# atmega16_laptop_keyboard.net
KiCad netlist of a schematic drawn in EAGLE
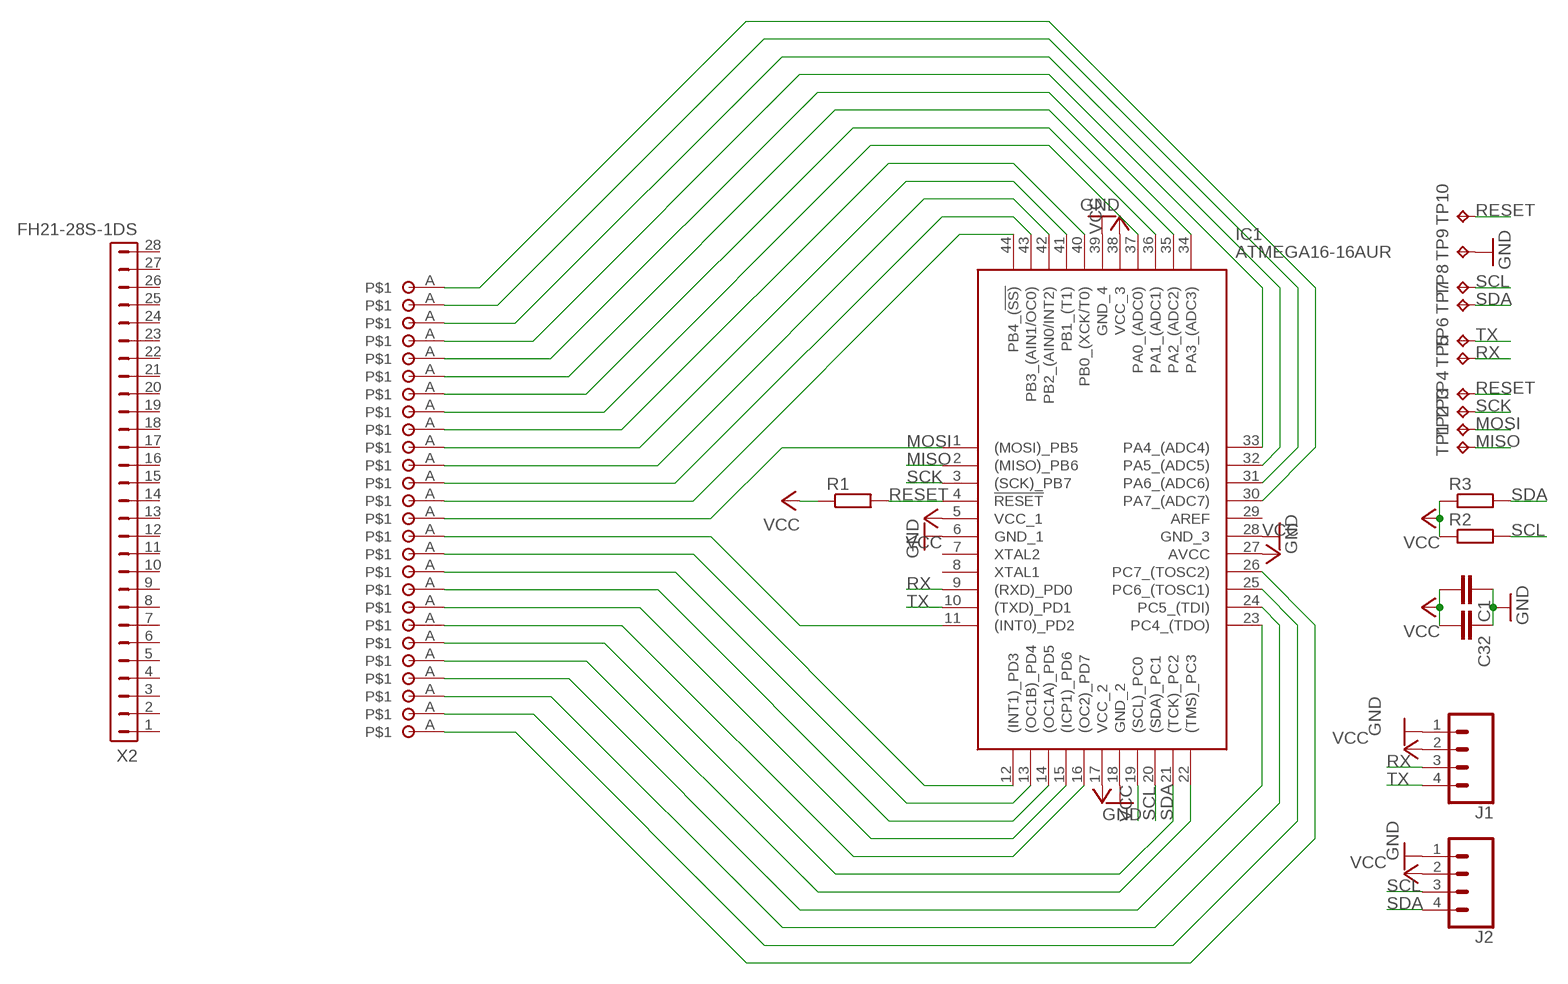
[diagram p0: schematic, sheet 1]

(export (version "E")
  (design (tool "Eeschema 10.0.6"))
  (components
    (comp (ref "C1")
      (value "C-EUC0805")
      (footprint "eagle-import:C0805")
      (libsource (lib "eagle-import") (part "C-EUC0805"))
    )
    (comp (ref "C32")
      (value "C-EUC0805")
      (footprint "eagle-import:C0805")
      (libsource (lib "eagle-import") (part "C-EUC0805"))
    )
    (comp (ref "IC1")
      (value "ATMEGA16-16AUR")
      (footprint "eagle-import:QFP80P1200X1200X120-44N")
      (fields (field (name "MOUSER_PART_NUMBER") "556-ATMEGA16-16AUR"))
      (libsource (lib "eagle-import") (part "ATMEGA16-16AUR"))
    )
    (comp (ref "J1")
      (value "CONN_04LONGPADS")
      (footprint "eagle-import:1X04_LONGPADS")
      (libsource (lib "eagle-import") (part "CONN_04LONGPADS"))
    )
    (comp (ref "J2")
      (value "CONN_04LONGPADS")
      (footprint "eagle-import:1X04_LONGPADS")
      (libsource (lib "eagle-import") (part "CONN_04LONGPADS"))
    )
    (comp (ref "R1")
      (value "R-EU_M0805")
      (footprint "eagle-import:M0805")
      (libsource (lib "eagle-import") (part "R-EU_M0805"))
    )
    (comp (ref "R2")
      (value "R-EU_M0805")
      (footprint "eagle-import:M0805")
      (libsource (lib "eagle-import") (part "R-EU_M0805"))
    )
    (comp (ref "R3")
      (value "R-EU_M0805")
      (footprint "eagle-import:M0805")
      (libsource (lib "eagle-import") (part "R-EU_M0805"))
    )
    (comp (ref "TP1")
      (value "TPTP15R")
      (footprint "eagle-import:TP15R")
      (libsource (lib "eagle-import") (part "TPTP15R"))
    )
    (comp (ref "TP2")
      (value "TPTP15R")
      (footprint "eagle-import:TP15R")
      (libsource (lib "eagle-import") (part "TPTP15R"))
    )
    (comp (ref "TP3")
      (value "TPTP15R")
      (footprint "eagle-import:TP15R")
      (libsource (lib "eagle-import") (part "TPTP15R"))
    )
    (comp (ref "TP4")
      (value "TPTP15R")
      (footprint "eagle-import:TP15R")
      (libsource (lib "eagle-import") (part "TPTP15R"))
    )
    (comp (ref "TP5")
      (value "TPTP15R")
      (footprint "eagle-import:TP15R")
      (libsource (lib "eagle-import") (part "TPTP15R"))
    )
    (comp (ref "TP6")
      (value "TPTP15R")
      (footprint "eagle-import:TP15R")
      (libsource (lib "eagle-import") (part "TPTP15R"))
    )
    (comp (ref "TP7")
      (value "TPTP15R")
      (footprint "eagle-import:TP15R")
      (libsource (lib "eagle-import") (part "TPTP15R"))
    )
    (comp (ref "TP8")
      (value "TPTP15R")
      (footprint "eagle-import:TP15R")
      (libsource (lib "eagle-import") (part "TPTP15R"))
    )
    (comp (ref "TP9")
      (value "TPTP15R")
      (footprint "eagle-import:TP15R")
      (libsource (lib "eagle-import") (part "TPTP15R"))
    )
    (comp (ref "TP10")
      (value "TPTP15R")
      (footprint "eagle-import:TP15R")
      (libsource (lib "eagle-import") (part "TPTP15R"))
    )
    (comp (ref "U$1")
      (value "PAD1")
      (footprint "eagle-import:PAD1")
      (libsource (lib "eagle-import") (part "PAD1"))
    )
    (comp (ref "U$2")
      (value "PAD1")
      (footprint "eagle-import:PAD1")
      (libsource (lib "eagle-import") (part "PAD1"))
    )
    (comp (ref "U$3")
      (value "PAD1")
      (footprint "eagle-import:PAD1")
      (libsource (lib "eagle-import") (part "PAD1"))
    )
    (comp (ref "U$4")
      (value "PAD1")
      (footprint "eagle-import:PAD1")
      (libsource (lib "eagle-import") (part "PAD1"))
    )
    (comp (ref "U$5")
      (value "PAD1")
      (footprint "eagle-import:PAD1")
      (libsource (lib "eagle-import") (part "PAD1"))
    )
    (comp (ref "U$6")
      (value "PAD1")
      (footprint "eagle-import:PAD1")
      (libsource (lib "eagle-import") (part "PAD1"))
    )
    (comp (ref "U$7")
      (value "PAD1")
      (footprint "eagle-import:PAD1")
      (libsource (lib "eagle-import") (part "PAD1"))
    )
    (comp (ref "U$8")
      (value "PAD1")
      (footprint "eagle-import:PAD1")
      (libsource (lib "eagle-import") (part "PAD1"))
    )
    (comp (ref "U$9")
      (value "PAD1")
      (footprint "eagle-import:PAD1")
      (libsource (lib "eagle-import") (part "PAD1"))
    )
    (comp (ref "U$10")
      (value "PAD1")
      (footprint "eagle-import:PAD1")
      (libsource (lib "eagle-import") (part "PAD1"))
    )
    (comp (ref "U$11")
      (value "PAD1")
      (footprint "eagle-import:PAD1")
      (libsource (lib "eagle-import") (part "PAD1"))
    )
    (comp (ref "U$12")
      (value "PAD1")
      (footprint "eagle-import:PAD1")
      (libsource (lib "eagle-import") (part "PAD1"))
    )
    (comp (ref "U$13")
      (value "PAD1")
      (footprint "eagle-import:PAD1")
      (libsource (lib "eagle-import") (part "PAD1"))
    )
    (comp (ref "U$14")
      (value "PAD1")
      (footprint "eagle-import:PAD1")
      (libsource (lib "eagle-import") (part "PAD1"))
    )
    (comp (ref "U$15")
      (value "PAD1")
      (footprint "eagle-import:PAD1")
      (libsource (lib "eagle-import") (part "PAD1"))
    )
    (comp (ref "U$16")
      (value "PAD1")
      (footprint "eagle-import:PAD1")
      (libsource (lib "eagle-import") (part "PAD1"))
    )
    (comp (ref "U$17")
      (value "PAD1")
      (footprint "eagle-import:PAD1")
      (libsource (lib "eagle-import") (part "PAD1"))
    )
    (comp (ref "U$18")
      (value "PAD1")
      (footprint "eagle-import:PAD1")
      (libsource (lib "eagle-import") (part "PAD1"))
    )
    (comp (ref "U$19")
      (value "PAD1")
      (footprint "eagle-import:PAD1")
      (libsource (lib "eagle-import") (part "PAD1"))
    )
    (comp (ref "U$20")
      (value "PAD1")
      (footprint "eagle-import:PAD1")
      (libsource (lib "eagle-import") (part "PAD1"))
    )
    (comp (ref "U$21")
      (value "PAD1")
      (footprint "eagle-import:PAD1")
      (libsource (lib "eagle-import") (part "PAD1"))
    )
    (comp (ref "U$22")
      (value "PAD1")
      (footprint "eagle-import:PAD1")
      (libsource (lib "eagle-import") (part "PAD1"))
    )
    (comp (ref "U$23")
      (value "PAD1")
      (footprint "eagle-import:PAD1")
      (libsource (lib "eagle-import") (part "PAD1"))
    )
    (comp (ref "U$24")
      (value "PAD1")
      (footprint "eagle-import:PAD1")
      (libsource (lib "eagle-import") (part "PAD1"))
    )
    (comp (ref "U$25")
      (value "PAD1")
      (footprint "eagle-import:PAD1")
      (libsource (lib "eagle-import") (part "PAD1"))
    )
    (comp (ref "U$26")
      (value "PAD1")
      (footprint "eagle-import:PAD1")
      (libsource (lib "eagle-import") (part "PAD1"))
    )
    (comp (ref "X2")
      (value "FH21-28S-1DS")
      (footprint "eagle-import:FH21-28S-1DS")
      (libsource (lib "eagle-import") (part "FH21-28S-1DS"))
    )
  )
  (nets
    (net (code "1") (name "/MISO") (class "Default")
      (node (ref "IC1") (pin "2") (pinfunction "(MISO)_PB6_2") (pintype "bidirectional"))
      (node (ref "TP1") (pin "TP") (pinfunction "TP_TP") (pintype "input"))
    )
    (net (code "2") (name "/MOSI") (class "Default")
      (node (ref "IC1") (pin "1") (pinfunction "(MOSI)_PB5_1") (pintype "bidirectional"))
      (node (ref "TP2") (pin "TP") (pinfunction "TP_TP") (pintype "input"))
      (node (ref "U$14") (pin "A") (pinfunction "P$1_A") (pintype "bidirectional"))
    )
    (net (code "3") (name "/RESET") (class "Default")
      (node (ref "IC1") (pin "4") (pinfunction "~{RESET}_4") (pintype "bidirectional"))
      (node (ref "R1") (pin "2") (pinfunction "2_2") (pintype "passive"))
      (node (ref "TP10") (pin "TP") (pinfunction "TP_TP") (pintype "input"))
      (node (ref "TP4") (pin "TP") (pinfunction "TP_TP") (pintype "input"))
    )
    (net (code "4") (name "/RX") (class "Default")
      (node (ref "IC1") (pin "9") (pinfunction "(RXD)_PD0_9") (pintype "bidirectional"))
      (node (ref "J1") (pin "3") (pinfunction "3_3") (pintype "passive"))
      (node (ref "TP5") (pin "TP") (pinfunction "TP_TP") (pintype "input"))
    )
    (net (code "5") (name "/SCK") (class "Default")
      (node (ref "IC1") (pin "3") (pinfunction "(SCK)_PB7_3") (pintype "bidirectional"))
      (node (ref "TP3") (pin "TP") (pinfunction "TP_TP") (pintype "input"))
    )
    (net (code "6") (name "/SCL") (class "Default")
      (node (ref "IC1") (pin "19") (pinfunction "(SCL)_PC0_19") (pintype "bidirectional"))
      (node (ref "J2") (pin "3") (pinfunction "3_3") (pintype "passive"))
      (node (ref "R2") (pin "2") (pinfunction "2_2") (pintype "passive"))
      (node (ref "TP8") (pin "TP") (pinfunction "TP_TP") (pintype "input"))
    )
    (net (code "7") (name "/SDA") (class "Default")
      (node (ref "IC1") (pin "20") (pinfunction "(SDA)_PC1_20") (pintype "bidirectional"))
      (node (ref "J2") (pin "4") (pinfunction "4_4") (pintype "passive"))
      (node (ref "R3") (pin "2") (pinfunction "2_2") (pintype "passive"))
      (node (ref "TP7") (pin "TP") (pinfunction "TP_TP") (pintype "input"))
    )
    (net (code "8") (name "/TX") (class "Default")
      (node (ref "IC1") (pin "10") (pinfunction "(TXD)_PD1_10") (pintype "bidirectional"))
      (node (ref "J1") (pin "4") (pinfunction "4_4") (pintype "passive"))
      (node (ref "TP6") (pin "TP") (pinfunction "TP_TP") (pintype "input"))
    )
    (net (code "9") (name "GND") (class "Default")
      (node (ref "C1") (pin "1") (pinfunction "1_1") (pintype "passive"))
      (node (ref "C32") (pin "1") (pinfunction "1_1") (pintype "passive"))
      (node (ref "IC1") (pin "18") (pinfunction "GND_2_18") (pintype "bidirectional"))
      (node (ref "IC1") (pin "28") (pinfunction "GND_3_28") (pintype "bidirectional"))
      (node (ref "IC1") (pin "39") (pinfunction "GND_4_39") (pintype "bidirectional"))
      (node (ref "IC1") (pin "6") (pinfunction "GND_1_6") (pintype "bidirectional"))
      (node (ref "J1") (pin "1") (pinfunction "1_1") (pintype "passive"))
      (node (ref "J2") (pin "1") (pinfunction "1_1") (pintype "passive"))
      (node (ref "TP9") (pin "TP") (pinfunction "TP_TP") (pintype "input"))
    )
    (net (code "10") (name "Net-(IC1-(ICP1)_PD6)") (class "Default")
      (node (ref "IC1") (pin "15") (pinfunction "(ICP1)_PD6_15") (pintype "bidirectional"))
      (node (ref "U$19") (pin "A") (pinfunction "P$1_A") (pintype "bidirectional"))
    )
    (net (code "11") (name "Net-(IC1-(INT0)_PD2)") (class "Default")
      (node (ref "IC1") (pin "11") (pinfunction "(INT0)_PD2_11") (pintype "bidirectional"))
      (node (ref "U$15") (pin "A") (pinfunction "P$1_A") (pintype "bidirectional"))
    )
    (net (code "12") (name "Net-(IC1-(INT1)_PD3)") (class "Default")
      (node (ref "IC1") (pin "12") (pinfunction "(INT1)_PD3_12") (pintype "bidirectional"))
      (node (ref "U$16") (pin "A") (pinfunction "P$1_A") (pintype "bidirectional"))
    )
    (net (code "13") (name "Net-(IC1-(OC1A)_PD5)") (class "Default")
      (node (ref "IC1") (pin "14") (pinfunction "(OC1A)_PD5_14") (pintype "bidirectional"))
      (node (ref "U$18") (pin "A") (pinfunction "P$1_A") (pintype "bidirectional"))
    )
    (net (code "14") (name "Net-(IC1-(OC1B)_PD4)") (class "Default")
      (node (ref "IC1") (pin "13") (pinfunction "(OC1B)_PD4_13") (pintype "bidirectional"))
      (node (ref "U$17") (pin "A") (pinfunction "P$1_A") (pintype "bidirectional"))
    )
    (net (code "15") (name "Net-(IC1-(OC2)_PD7)") (class "Default")
      (node (ref "IC1") (pin "16") (pinfunction "(OC2)_PD7_16") (pintype "bidirectional"))
      (node (ref "U$20") (pin "A") (pinfunction "P$1_A") (pintype "bidirectional"))
    )
    (net (code "16") (name "Net-(IC1-(TCK)_PC2)") (class "Default")
      (node (ref "IC1") (pin "21") (pinfunction "(TCK)_PC2_21") (pintype "bidirectional"))
      (node (ref "U$21") (pin "A") (pinfunction "P$1_A") (pintype "bidirectional"))
    )
    (net (code "17") (name "Net-(IC1-(TMS)_PC3)") (class "Default")
      (node (ref "IC1") (pin "22") (pinfunction "(TMS)_PC3_22") (pintype "bidirectional"))
      (node (ref "U$22") (pin "A") (pinfunction "P$1_A") (pintype "bidirectional"))
    )
    (net (code "18") (name "Net-(IC1-PA0_(ADC0))") (class "Default")
      (node (ref "IC1") (pin "37") (pinfunction "PA0_(ADC0)_37") (pintype "bidirectional"))
      (node (ref "U$8") (pin "A") (pinfunction "P$1_A") (pintype "bidirectional"))
    )
    (net (code "19") (name "Net-(IC1-PA1_(ADC1))") (class "Default")
      (node (ref "IC1") (pin "36") (pinfunction "PA1_(ADC1)_36") (pintype "bidirectional"))
      (node (ref "U$7") (pin "A") (pinfunction "P$1_A") (pintype "bidirectional"))
    )
    (net (code "20") (name "Net-(IC1-PA2_(ADC2))") (class "Default")
      (node (ref "IC1") (pin "35") (pinfunction "PA2_(ADC2)_35") (pintype "bidirectional"))
      (node (ref "U$6") (pin "A") (pinfunction "P$1_A") (pintype "bidirectional"))
    )
    (net (code "21") (name "Net-(IC1-PA3_(ADC3))") (class "Default")
      (node (ref "IC1") (pin "34") (pinfunction "PA3_(ADC3)_34") (pintype "bidirectional"))
      (node (ref "U$5") (pin "A") (pinfunction "P$1_A") (pintype "bidirectional"))
    )
    (net (code "22") (name "Net-(IC1-PA4_(ADC4))") (class "Default")
      (node (ref "IC1") (pin "33") (pinfunction "PA4_(ADC4)_33") (pintype "bidirectional"))
      (node (ref "U$4") (pin "A") (pinfunction "P$1_A") (pintype "bidirectional"))
    )
    (net (code "23") (name "Net-(IC1-PA5_(ADC5))") (class "Default")
      (node (ref "IC1") (pin "32") (pinfunction "PA5_(ADC5)_32") (pintype "bidirectional"))
      (node (ref "U$3") (pin "A") (pinfunction "P$1_A") (pintype "bidirectional"))
    )
    (net (code "24") (name "Net-(IC1-PA6_(ADC6))") (class "Default")
      (node (ref "IC1") (pin "31") (pinfunction "PA6_(ADC6)_31") (pintype "bidirectional"))
      (node (ref "U$2") (pin "A") (pinfunction "P$1_A") (pintype "bidirectional"))
    )
    (net (code "25") (name "Net-(IC1-PA7_(ADC7))") (class "Default")
      (node (ref "IC1") (pin "30") (pinfunction "PA7_(ADC7)_30") (pintype "bidirectional"))
      (node (ref "U$1") (pin "A") (pinfunction "P$1_A") (pintype "bidirectional"))
    )
    (net (code "26") (name "Net-(IC1-PB0_(XCK{slash}T0))") (class "Default")
      (node (ref "IC1") (pin "40") (pinfunction "PB0_(XCK/T0)_40") (pintype "bidirectional"))
      (node (ref "U$9") (pin "A") (pinfunction "P$1_A") (pintype "bidirectional"))
    )
    (net (code "27") (name "Net-(IC1-PB1_(T1))") (class "Default")
      (node (ref "IC1") (pin "41") (pinfunction "PB1_(T1)_41") (pintype "bidirectional"))
      (node (ref "U$10") (pin "A") (pinfunction "P$1_A") (pintype "bidirectional"))
    )
    (net (code "28") (name "Net-(IC1-PB2_(AIN0{slash}INT2))") (class "Default")
      (node (ref "IC1") (pin "42") (pinfunction "PB2_(AIN0/INT2)_42") (pintype "bidirectional"))
      (node (ref "U$11") (pin "A") (pinfunction "P$1_A") (pintype "bidirectional"))
    )
    (net (code "29") (name "Net-(IC1-PB3_(AIN1{slash}OC0))") (class "Default")
      (node (ref "IC1") (pin "43") (pinfunction "PB3_(AIN1/OC0)_43") (pintype "bidirectional"))
      (node (ref "U$12") (pin "A") (pinfunction "P$1_A") (pintype "bidirectional"))
    )
    (net (code "30") (name "Net-(IC1-PB4_(~{SS}))") (class "Default")
      (node (ref "IC1") (pin "44") (pinfunction "PB4_(~{SS})_44") (pintype "bidirectional"))
      (node (ref "U$13") (pin "A") (pinfunction "P$1_A") (pintype "bidirectional"))
    )
    (net (code "31") (name "Net-(IC1-PC4_(TDO))") (class "Default")
      (node (ref "IC1") (pin "23") (pinfunction "PC4_(TDO)_23") (pintype "bidirectional"))
      (node (ref "U$23") (pin "A") (pinfunction "P$1_A") (pintype "bidirectional"))
    )
    (net (code "32") (name "Net-(IC1-PC5_(TDI))") (class "Default")
      (node (ref "IC1") (pin "24") (pinfunction "PC5_(TDI)_24") (pintype "bidirectional"))
      (node (ref "U$24") (pin "A") (pinfunction "P$1_A") (pintype "bidirectional"))
    )
    (net (code "33") (name "Net-(IC1-PC6_(TOSC1))") (class "Default")
      (node (ref "IC1") (pin "25") (pinfunction "PC6_(TOSC1)_25") (pintype "bidirectional"))
      (node (ref "U$25") (pin "A") (pinfunction "P$1_A") (pintype "bidirectional"))
    )
    (net (code "34") (name "Net-(IC1-PC7_(TOSC2))") (class "Default")
      (node (ref "IC1") (pin "26") (pinfunction "PC7_(TOSC2)_26") (pintype "bidirectional"))
      (node (ref "U$26") (pin "A") (pinfunction "P$1_A") (pintype "bidirectional"))
    )
    (net (code "35") (name "VCC") (class "Default")
      (node (ref "C1") (pin "2") (pinfunction "2_2") (pintype "passive"))
      (node (ref "C32") (pin "2") (pinfunction "2_2") (pintype "passive"))
      (node (ref "IC1") (pin "17") (pinfunction "VCC_2_17") (pintype "bidirectional"))
      (node (ref "IC1") (pin "27") (pinfunction "AVCC_27") (pintype "bidirectional"))
      (node (ref "IC1") (pin "38") (pinfunction "VCC_3_38") (pintype "bidirectional"))
      (node (ref "IC1") (pin "5") (pinfunction "VCC_1_5") (pintype "bidirectional"))
      (node (ref "J1") (pin "2") (pinfunction "2_2") (pintype "passive"))
      (node (ref "J2") (pin "2") (pinfunction "2_2") (pintype "passive"))
      (node (ref "R1") (pin "1") (pinfunction "1_1") (pintype "passive"))
      (node (ref "R2") (pin "1") (pinfunction "1_1") (pintype "passive"))
      (node (ref "R3") (pin "1") (pinfunction "1_1") (pintype "passive"))
    )
    (net (code "36") (name "unconnected-(IC1-AREF-Pad29)") (class "Default")
      (node (ref "IC1") (pin "29") (pinfunction "AREF_29") (pintype "bidirectional"))
    )
    (net (code "37") (name "unconnected-(IC1-XTAL1-Pad8)") (class "Default")
      (node (ref "IC1") (pin "8") (pinfunction "XTAL1_8") (pintype "bidirectional"))
    )
    (net (code "38") (name "unconnected-(IC1-XTAL2-Pad7)") (class "Default")
      (node (ref "IC1") (pin "7") (pinfunction "XTAL2_7") (pintype "bidirectional"))
    )
    (net (code "39") (name "unconnected-(X2-Pad1)") (class "Default")
      (node (ref "X2") (pin "1") (pinfunction "1_1") (pintype "passive"))
    )
    (net (code "40") (name "unconnected-(X2-Pad2)") (class "Default")
      (node (ref "X2") (pin "2") (pinfunction "2_2") (pintype "passive"))
    )
    (net (code "41") (name "unconnected-(X2-Pad3)") (class "Default")
      (node (ref "X2") (pin "3") (pinfunction "3_3") (pintype "passive"))
    )
    (net (code "42") (name "unconnected-(X2-Pad4)") (class "Default")
      (node (ref "X2") (pin "4") (pinfunction "4_4") (pintype "passive"))
    )
    (net (code "43") (name "unconnected-(X2-Pad5)") (class "Default")
      (node (ref "X2") (pin "5") (pinfunction "5_5") (pintype "passive"))
    )
    (net (code "44") (name "unconnected-(X2-Pad6)") (class "Default")
      (node (ref "X2") (pin "6") (pinfunction "6_6") (pintype "passive"))
    )
    (net (code "45") (name "unconnected-(X2-Pad7)") (class "Default")
      (node (ref "X2") (pin "7") (pinfunction "7_7") (pintype "passive"))
    )
    (net (code "46") (name "unconnected-(X2-Pad8)") (class "Default")
      (node (ref "X2") (pin "8") (pinfunction "8_8") (pintype "passive"))
    )
    (net (code "47") (name "unconnected-(X2-Pad9)") (class "Default")
      (node (ref "X2") (pin "9") (pinfunction "9_9") (pintype "passive"))
    )
    (net (code "48") (name "unconnected-(X2-Pad10)") (class "Default")
      (node (ref "X2") (pin "10") (pinfunction "10_10") (pintype "passive"))
    )
    (net (code "49") (name "unconnected-(X2-Pad11)") (class "Default")
      (node (ref "X2") (pin "11") (pinfunction "11_11") (pintype "passive"))
    )
    (net (code "50") (name "unconnected-(X2-Pad12)") (class "Default")
      (node (ref "X2") (pin "12") (pinfunction "12_12") (pintype "passive"))
    )
    (net (code "51") (name "unconnected-(X2-Pad13)") (class "Default")
      (node (ref "X2") (pin "13") (pinfunction "13_13") (pintype "passive"))
    )
    (net (code "52") (name "unconnected-(X2-Pad14)") (class "Default")
      (node (ref "X2") (pin "14") (pinfunction "14_14") (pintype "passive"))
    )
    (net (code "53") (name "unconnected-(X2-Pad15)") (class "Default")
      (node (ref "X2") (pin "15") (pinfunction "15_15") (pintype "passive"))
    )
    (net (code "54") (name "unconnected-(X2-Pad16)") (class "Default")
      (node (ref "X2") (pin "16") (pinfunction "16_16") (pintype "passive"))
    )
    (net (code "55") (name "unconnected-(X2-Pad17)") (class "Default")
      (node (ref "X2") (pin "17") (pinfunction "17_17") (pintype "passive"))
    )
    (net (code "56") (name "unconnected-(X2-Pad18)") (class "Default")
      (node (ref "X2") (pin "18") (pinfunction "18_18") (pintype "passive"))
    )
    (net (code "57") (name "unconnected-(X2-Pad19)") (class "Default")
      (node (ref "X2") (pin "19") (pinfunction "19_19") (pintype "passive"))
    )
    (net (code "58") (name "unconnected-(X2-Pad20)") (class "Default")
      (node (ref "X2") (pin "20") (pinfunction "20_20") (pintype "passive"))
    )
    (net (code "59") (name "unconnected-(X2-Pad21)") (class "Default")
      (node (ref "X2") (pin "21") (pinfunction "21_21") (pintype "passive"))
    )
    (net (code "60") (name "unconnected-(X2-Pad22)") (class "Default")
      (node (ref "X2") (pin "22") (pinfunction "22_22") (pintype "passive"))
    )
    (net (code "61") (name "unconnected-(X2-Pad23)") (class "Default")
      (node (ref "X2") (pin "23") (pinfunction "23_23") (pintype "passive"))
    )
    (net (code "62") (name "unconnected-(X2-Pad24)") (class "Default")
      (node (ref "X2") (pin "24") (pinfunction "24_24") (pintype "passive"))
    )
    (net (code "63") (name "unconnected-(X2-Pad25)") (class "Default")
      (node (ref "X2") (pin "25") (pinfunction "25_25") (pintype "passive"))
    )
    (net (code "64") (name "unconnected-(X2-Pad26)") (class "Default")
      (node (ref "X2") (pin "26") (pinfunction "26_26") (pintype "passive"))
    )
    (net (code "65") (name "unconnected-(X2-Pad27)") (class "Default")
      (node (ref "X2") (pin "27") (pinfunction "27_27") (pintype "passive"))
    )
    (net (code "66") (name "unconnected-(X2-Pad28)") (class "Default")
      (node (ref "X2") (pin "28") (pinfunction "28_28") (pintype "passive"))
    )
  )
)
